# can-transceiver.net
KiCad netlist of a schematic drawn in Altium Designer
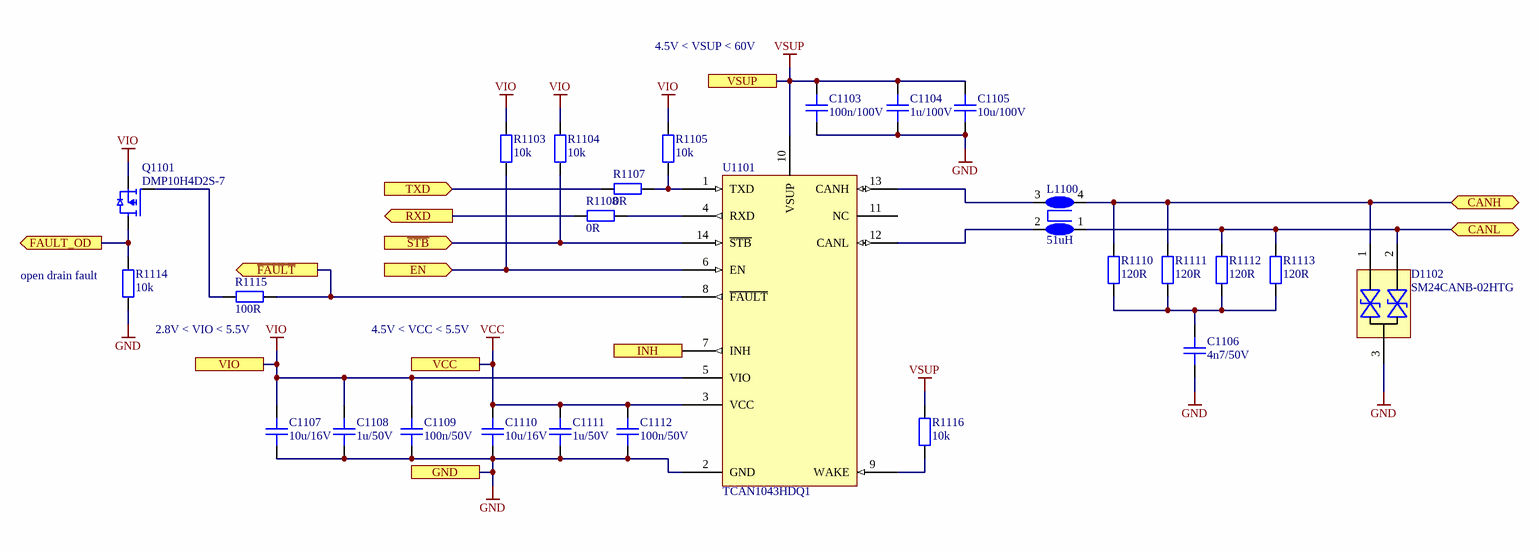
[diagram p0: can-transceiver.SchDoc]

(export (version "E")
  (design (tool "Eeschema 10.0.6"))
  (components
    (comp (ref "C1103")
      (value "100n/100V")
      (footprint "CAPC1608X08N")
      (description "MLCC")
      (fields (field (name "PART NUMBER") "gen_C_ceramic_100n_100V_X7R_0603"))
      (libsource (lib "OE750") (part "C"))
    )
    (comp (ref "C1104")
      (value "1u/100V")
      (footprint "CAPC3216X18N")
      (description "MLCC")
      (fields (field (name "PART NUMBER") "gen_C_ceramic_1u_100V_X7R_1206"))
      (libsource (lib "OE750") (part "C"))
    )
    (comp (ref "C1105")
      (value "10u/100V")
      (footprint "CAPC5750X28N")
      (description "MLCC")
      (fields (field (name "PART NUMBER") "gen_C_ceramic_10u_100V_X7S_2220"))
      (libsource (lib "OE750") (part "C"))
    )
    (comp (ref "C1106")
      (value "4n7/50V")
      (footprint "CAPC1005X06N")
      (description "MLCC")
      (fields (field (name "PART NUMBER") "gen_C_ceramic_4n7_50V_X7R_0402"))
      (libsource (lib "OE750") (part "C"))
    )
    (comp (ref "C1107")
      (value "10u/16V")
      (footprint "CAPC2012X14N")
      (description "MLCC")
      (fields (field (name "PART NUMBER") "gen_C_ceramic_10u_16V_X7R_0805"))
      (libsource (lib "OE750") (part "C"))
    )
    (comp (ref "C1108")
      (value "1u/50V")
      (footprint "CAPC1608X08N")
      (description "MLCC")
      (fields (field (name "PART NUMBER") "gen_C_ceramic_1u_50V_X7R_0603") (field (name "TOLERANCE") "± 10%"))
      (libsource (lib "OE750") (part "C"))
    )
    (comp (ref "C1109")
      (value "100n/50V")
      (footprint "CAPC1005X06N")
      (description "MLCC")
      (fields (field (name "PART NUMBER") "gen_C_ceramic_100n_50V_X7R_0402"))
      (libsource (lib "OE750") (part "C"))
    )
    (comp (ref "C1110")
      (value "10u/16V")
      (footprint "CAPC2012X14N")
      (description "MLCC")
      (fields (field (name "PART NUMBER") "gen_C_ceramic_10u_16V_X7R_0805"))
      (libsource (lib "OE750") (part "C"))
    )
    (comp (ref "C1111")
      (value "1u/50V")
      (footprint "CAPC1608X08N")
      (description "MLCC")
      (fields (field (name "PART NUMBER") "gen_C_ceramic_1u_50V_X7R_0603") (field (name "TOLERANCE") "± 10%"))
      (libsource (lib "OE750") (part "C"))
    )
    (comp (ref "C1112")
      (value "100n/50V")
      (footprint "CAPC1005X06N")
      (description "MLCC")
      (fields (field (name "PART NUMBER") "gen_C_ceramic_100n_50V_X7R_0402"))
      (libsource (lib "OE750") (part "C"))
    )
    (comp (ref "D1102")
      (value "SM24CANB-02HTG")
      (footprint "LF_SOT23-3")
      (description "CAN ESD Protection Diode Array")
      (fields (field (name "MANUFACTURER") "Littelfuse"))
      (libsource (lib "OE750") (part "SM24CANB"))
    )
    (comp (ref "L1100")
      (value "51uH")
      (footprint "MURATA_DLW32SH")
      (description "Common Mode Choke")
      (fields (field (name "PART NUMBER") "DLW32SH510XK2L") (field (name "MANUFACTURER") "Murata"))
      (libsource (lib "OE750") (part "L_CM"))
    )
    (comp (ref "Q1101")
      (value "DMP10H4D2S-7")
      (footprint "SOT95P237X110-3N")
      (description "MOSFET-Transistor, p-Kanal, 0.27 A, 100 V, 4.2 ohm")
      (fields (field (name "MANUFACTURER") "Diodes"))
      (libsource (lib "OE750") (part "PMOS"))
    )
    (comp (ref "R1103")
      (value "10k")
      (footprint "RESC1005X04N")
      (description "SMD Resistor 10k 0402")
      (fields (field (name "PART NUMBER") "gen_R_10k_0402") (field (name "TOLERANCE") "1%"))
      (libsource (lib "OE750") (part "R"))
    )
    (comp (ref "R1104")
      (value "10k")
      (footprint "RESC1005X04N")
      (description "SMD Resistor 10k 0402")
      (fields (field (name "PART NUMBER") "gen_R_10k_0402") (field (name "TOLERANCE") "1%"))
      (libsource (lib "OE750") (part "R"))
    )
    (comp (ref "R1105")
      (value "10k")
      (footprint "RESC1005X04N")
      (description "SMD Resistor 10k 0402")
      (fields (field (name "PART NUMBER") "gen_R_10k_0402") (field (name "TOLERANCE") "1%"))
      (libsource (lib "OE750") (part "R"))
    )
    (comp (ref "R1107")
      (value "0R")
      (footprint "RESC1005X04N")
      (description "SMD Resistor 0R 0402")
      (fields (field (name "PART NUMBER") "gen_R_0R_0402") (field (name "POWER") "0.063W"))
      (libsource (lib "OE750") (part "R"))
    )
    (comp (ref "R1108")
      (value "0R")
      (footprint "RESC1005X04N")
      (description "SMD Resistor 0R 0402")
      (fields (field (name "PART NUMBER") "gen_R_0R_0402") (field (name "POWER") "0.063W"))
      (libsource (lib "OE750") (part "R"))
    )
    (comp (ref "R1110")
      (value "120R")
      (footprint "RESC3216X06N")
      (description "SMD Resistor 120R 1206")
      (fields (field (name "PART NUMBER") "gen_R_120R_1206") (field (name "TOLERANCE") "1%"))
      (libsource (lib "OE750") (part "R"))
    )
    (comp (ref "R1111")
      (value "120R")
      (footprint "RESC3216X06N")
      (description "SMD Resistor 120R 1206")
      (fields (field (name "PART NUMBER") "gen_R_120R_1206") (field (name "TOLERANCE") "1%"))
      (libsource (lib "OE750") (part "R"))
    )
    (comp (ref "R1112")
      (value "120R")
      (footprint "RESC3216X06N")
      (description "SMD Resistor 120R 1206")
      (fields (field (name "PART NUMBER") "gen_R_120R_1206") (field (name "TOLERANCE") "1%"))
      (libsource (lib "OE750") (part "R"))
    )
    (comp (ref "R1113")
      (value "120R")
      (footprint "RESC3216X06N")
      (description "SMD Resistor 120R 1206")
      (fields (field (name "PART NUMBER") "gen_R_120R_1206") (field (name "TOLERANCE") "1%"))
      (libsource (lib "OE750") (part "R"))
    )
    (comp (ref "R1114")
      (value "10k")
      (footprint "RESC1005X04N")
      (description "SMD Resistor 10k 0402")
      (fields (field (name "PART NUMBER") "gen_R_10k_0402") (field (name "TOLERANCE") "1%"))
      (libsource (lib "OE750") (part "R"))
    )
    (comp (ref "R1115")
      (value "100R")
      (footprint "RESC1005X04N")
      (description "SMD Resistor 100R 0402")
      (fields (field (name "PART NUMBER") "gen_R_100R_0402") (field (name "TOLERANCE") "1%"))
      (libsource (lib "OE750") (part "R"))
    )
    (comp (ref "R1116")
      (value "10k")
      (footprint "RESC1005X04N")
      (description "SMD Resistor 10k 0402")
      (fields (field (name "PART NUMBER") "gen_R_10k_0402") (field (name "TOLERANCE") "1%"))
      (libsource (lib "OE750") (part "R"))
    )
    (comp (ref "U1101")
      (value "TCAN1043HDQ1")
      (footprint "TI_D0014A-C01_SOIC-14")
      (description "Low-Power Fault Protected CAN Transceiver with CAN FD and Wake")
      (fields (field (name "MANUFACTURER") "Texas Instruments"))
      (libsource (lib "OE750") (part "TCAN1043_SOIC14"))
    )
  )
  (nets
    (net (code "1") (name "/CANH") (class "Default")
      (node (ref "D1102") (pin "1") (pintype "passive"))
      (node (ref "L1100") (pin "4") (pinfunction "4_4") (pintype "passive"))
      (node (ref "R1110") (pin "2") (pinfunction "2_2") (pintype "passive"))
      (node (ref "R1111") (pin "2") (pinfunction "2_2") (pintype "passive"))
    )
    (net (code "2") (name "/CANL") (class "Default")
      (node (ref "D1102") (pin "2") (pintype "passive"))
      (node (ref "L1100") (pin "1") (pinfunction "1_1") (pintype "passive"))
      (node (ref "R1112") (pin "2") (pinfunction "2_2") (pintype "passive"))
      (node (ref "R1113") (pin "2") (pinfunction "2_2") (pintype "passive"))
    )
    (net (code "3") (name "/EN") (class "Default")
      (node (ref "R1103") (pin "1") (pinfunction "1_1") (pintype "passive"))
      (node (ref "U1101") (pin "6") (pinfunction "EN_6") (pintype "input"))
    )
    (net (code "4") (name "/FAULT") (class "Default")
      (node (ref "R1115") (pin "2") (pinfunction "2_2") (pintype "passive"))
      (node (ref "U1101") (pin "8") (pinfunction "FAULT_8") (pintype "output"))
    )
    (net (code "5") (name "/FAULT_OD") (class "Default")
      (node (ref "Q1101") (pin "D") (pinfunction "D_D") (pintype "passive"))
      (node (ref "R1114") (pin "2") (pinfunction "2_2") (pintype "passive"))
    )
    (net (code "6") (name "/INH") (class "Default")
      (node (ref "U1101") (pin "7") (pinfunction "INH_7") (pintype "output"))
    )
    (net (code "7") (name "/RXD") (class "Default")
      (node (ref "R1108") (pin "1") (pinfunction "1_1") (pintype "passive"))
    )
    (net (code "8") (name "/STB") (class "Default")
      (node (ref "R1104") (pin "1") (pinfunction "1_1") (pintype "passive"))
      (node (ref "U1101") (pin "14") (pinfunction "STB_14") (pintype "input"))
    )
    (net (code "9") (name "/TXD") (class "Default")
      (node (ref "R1107") (pin "1") (pinfunction "1_1") (pintype "passive"))
    )
    (net (code "10") (name "GND") (class "Default")
      (node (ref "C1103") (pin "1") (pinfunction "1_1") (pintype "passive"))
      (node (ref "C1104") (pin "1") (pinfunction "1_1") (pintype "passive"))
      (node (ref "C1105") (pin "1") (pinfunction "1_1") (pintype "passive"))
      (node (ref "C1106") (pin "1") (pinfunction "1_1") (pintype "passive"))
      (node (ref "C1107") (pin "1") (pinfunction "1_1") (pintype "passive"))
      (node (ref "C1108") (pin "1") (pinfunction "1_1") (pintype "passive"))
      (node (ref "C1109") (pin "1") (pinfunction "1_1") (pintype "passive"))
      (node (ref "C1110") (pin "1") (pinfunction "1_1") (pintype "passive"))
      (node (ref "C1111") (pin "1") (pinfunction "1_1") (pintype "passive"))
      (node (ref "C1112") (pin "1") (pinfunction "1_1") (pintype "passive"))
      (node (ref "D1102") (pin "3") (pintype "power_in"))
      (node (ref "R1114") (pin "1") (pinfunction "1_1") (pintype "passive"))
      (node (ref "U1101") (pin "2") (pinfunction "GND_2") (pintype "power_in"))
    )
    (net (code "11") (name "Net-(C1106-Pad2)") (class "Default")
      (node (ref "C1106") (pin "2") (pinfunction "2_2") (pintype "passive"))
      (node (ref "R1110") (pin "1") (pinfunction "1_1") (pintype "passive"))
      (node (ref "R1111") (pin "1") (pinfunction "1_1") (pintype "passive"))
      (node (ref "R1112") (pin "1") (pinfunction "1_1") (pintype "passive"))
      (node (ref "R1113") (pin "1") (pinfunction "1_1") (pintype "passive"))
    )
    (net (code "12") (name "Net-(Q1101-PadG)") (class "Default")
      (node (ref "Q1101") (pin "G") (pinfunction "G_G") (pintype "passive"))
      (node (ref "R1115") (pin "1") (pinfunction "1_1") (pintype "passive"))
    )
    (net (code "13") (name "Net-(U1101-CANH)") (class "Default")
      (node (ref "L1100") (pin "3") (pinfunction "3_3") (pintype "passive"))
      (node (ref "U1101") (pin "13") (pinfunction "CANH_13") (pintype "bidirectional"))
    )
    (net (code "14") (name "Net-(U1101-CANL)") (class "Default")
      (node (ref "L1100") (pin "2") (pinfunction "2_2") (pintype "passive"))
      (node (ref "U1101") (pin "12") (pinfunction "CANL_12") (pintype "bidirectional"))
    )
    (net (code "15") (name "Net-(U1101-RXD)") (class "Default")
      (node (ref "R1108") (pin "2") (pinfunction "2_2") (pintype "passive"))
      (node (ref "U1101") (pin "4") (pinfunction "RXD_4") (pintype "output"))
    )
    (net (code "16") (name "Net-(U1101-TXD)") (class "Default")
      (node (ref "R1105") (pin "1") (pinfunction "1_1") (pintype "passive"))
      (node (ref "R1107") (pin "2") (pinfunction "2_2") (pintype "passive"))
      (node (ref "U1101") (pin "1") (pinfunction "TXD_1") (pintype "input"))
    )
    (net (code "17") (name "Net-(U1101-WAKE)") (class "Default")
      (node (ref "R1116") (pin "1") (pinfunction "1_1") (pintype "passive"))
      (node (ref "U1101") (pin "9") (pinfunction "WAKE_9") (pintype "input"))
    )
    (net (code "18") (name "VCC") (class "Default")
      (node (ref "C1110") (pin "2") (pinfunction "2_2") (pintype "passive"))
      (node (ref "C1111") (pin "2") (pinfunction "2_2") (pintype "passive"))
      (node (ref "C1112") (pin "2") (pinfunction "2_2") (pintype "passive"))
      (node (ref "U1101") (pin "3") (pinfunction "VCC_3") (pintype "power_in"))
    )
    (net (code "19") (name "VIO") (class "Default")
      (node (ref "C1107") (pin "2") (pinfunction "2_2") (pintype "passive"))
      (node (ref "C1108") (pin "2") (pinfunction "2_2") (pintype "passive"))
      (node (ref "C1109") (pin "2") (pinfunction "2_2") (pintype "passive"))
      (node (ref "Q1101") (pin "S") (pinfunction "S_S") (pintype "passive"))
      (node (ref "R1103") (pin "2") (pinfunction "2_2") (pintype "passive"))
      (node (ref "R1104") (pin "2") (pinfunction "2_2") (pintype "passive"))
      (node (ref "R1105") (pin "2") (pinfunction "2_2") (pintype "passive"))
      (node (ref "U1101") (pin "5") (pinfunction "VIO_5") (pintype "power_in"))
    )
    (net (code "20") (name "VSUP") (class "Default")
      (node (ref "C1103") (pin "2") (pinfunction "2_2") (pintype "passive"))
      (node (ref "C1104") (pin "2") (pinfunction "2_2") (pintype "passive"))
      (node (ref "C1105") (pin "2") (pinfunction "2_2") (pintype "passive"))
      (node (ref "R1116") (pin "2") (pinfunction "2_2") (pintype "passive"))
      (node (ref "U1101") (pin "10") (pinfunction "VSUP_10") (pintype "power_in"))
    )
    (net (code "21") (name "unconnected-(U1101-NC-Pad11)") (class "Default")
      (node (ref "U1101") (pin "11") (pinfunction "NC_11") (pintype "passive"))
    )
  )
)
